# edison_gpio.net
KiCad netlist of a schematic drawn in Altium Designer
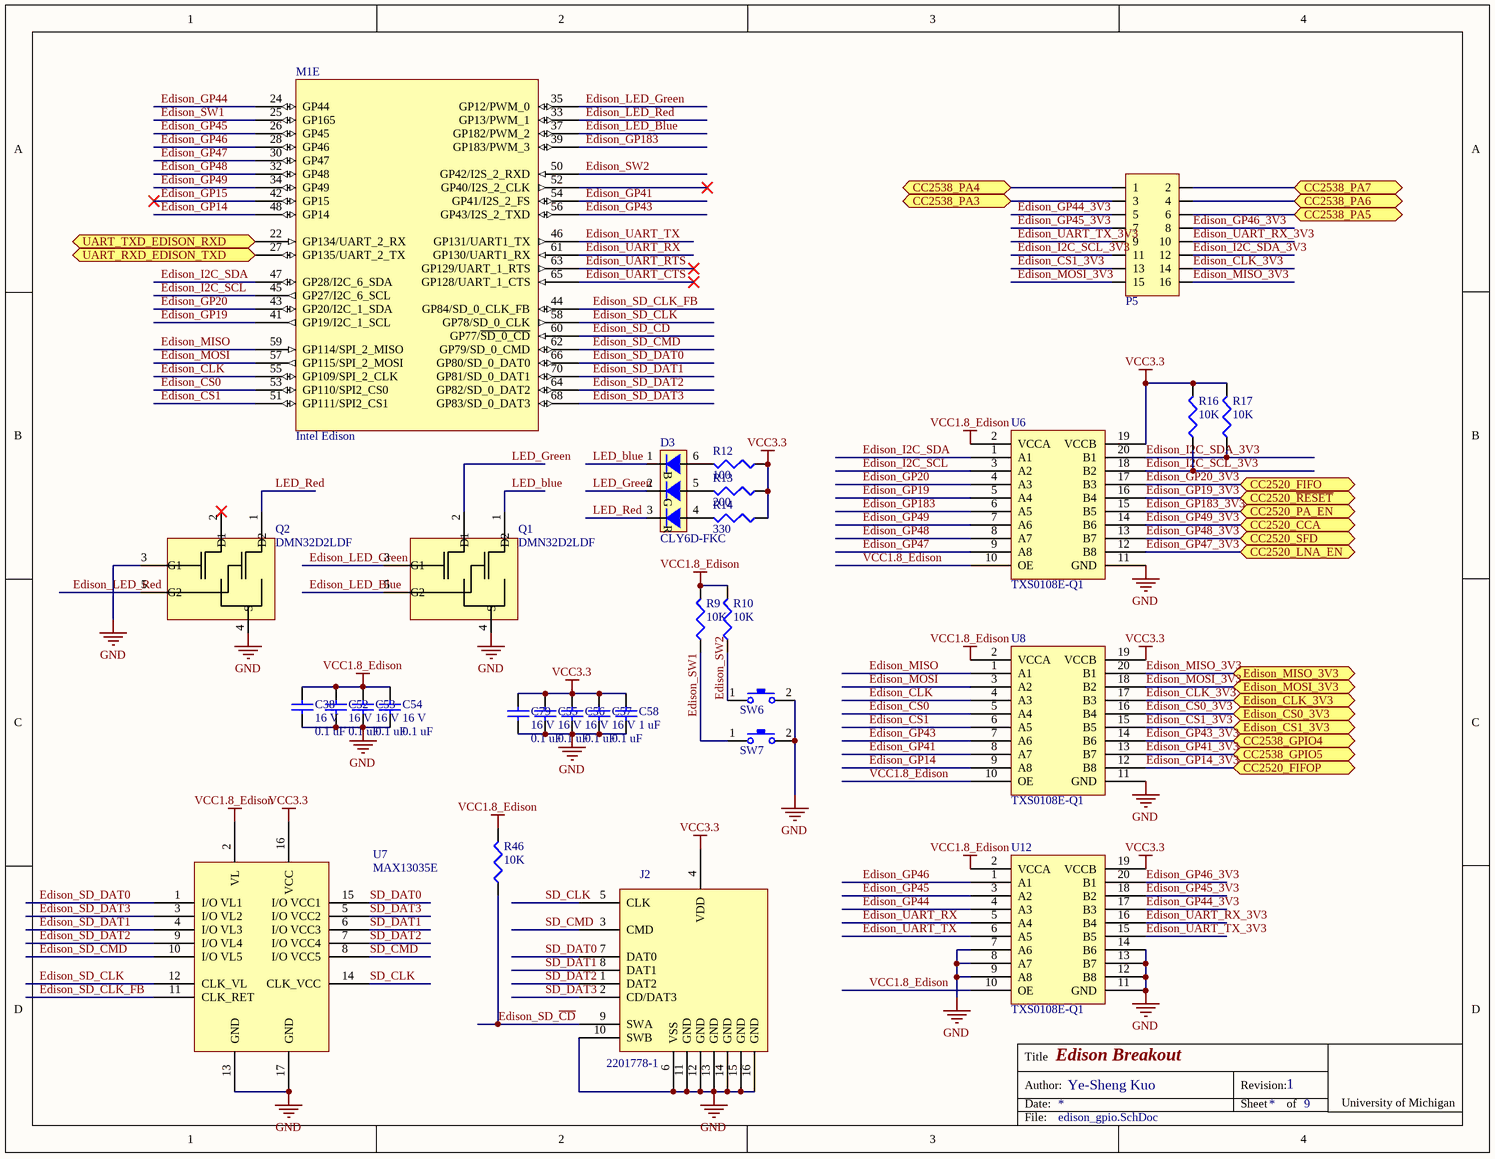
[diagram p0: edison_gpio.SchDoc]

(export (version "E")
  (design (tool "Eeschema 10.0.6"))
  (components
    (comp (ref "C38")
      (value "0.1 uF")
      (footprint "0402")
      (description "Ceramic capacitor, 0.1u, 16 V, 0402 package")
      (fields
        (field (name "VOLTAGE RATED") "16 V")
        (field (name "TOLERANCE") "10%")
        (field (name "Comment") "Ceramic capacitor")
      )
      (libsource (lib "rlc") (part "C_0.1u_16V_0402_ceramic"))
    )
    (comp (ref "C52")
      (value "0.1 uF")
      (footprint "0402")
      (description "Ceramic capacitor, 0.1u, 16 V, 0402 package")
      (fields
        (field (name "VOLTAGE RATED") "16 V")
        (field (name "TOLERANCE") "10%")
        (field (name "Comment") "Ceramic capacitor")
      )
      (libsource (lib "rlc") (part "C_0.1u_16V_0402_ceramic"))
    )
    (comp (ref "C53")
      (value "0.1 uF")
      (footprint "0402")
      (description "Ceramic capacitor, 0.1u, 16 V, 0402 package")
      (fields
        (field (name "VOLTAGE RATED") "16 V")
        (field (name "TOLERANCE") "10%")
        (field (name "Comment") "Ceramic capacitor")
      )
      (libsource (lib "rlc") (part "C_0.1u_16V_0402_ceramic"))
    )
    (comp (ref "C54")
      (value "0.1 uF")
      (footprint "0402")
      (description "Ceramic capacitor, 0.1u, 16 V, 0402 package")
      (fields
        (field (name "VOLTAGE RATED") "16 V")
        (field (name "TOLERANCE") "10%")
        (field (name "Comment") "Ceramic capacitor")
      )
      (libsource (lib "rlc") (part "C_0.1u_16V_0402_ceramic"))
    )
    (comp (ref "C55")
      (value "0.1 uF")
      (footprint "0402")
      (description "Ceramic capacitor, 0.1u, 16 V, 0402 package")
      (fields
        (field (name "VOLTAGE RATED") "16 V")
        (field (name "TOLERANCE") "10%")
        (field (name "Comment") "Ceramic capacitor")
      )
      (libsource (lib "rlc") (part "C_0.1u_16V_0402_ceramic"))
    )
    (comp (ref "C56")
      (value "0.1 uF")
      (footprint "0402")
      (description "Ceramic capacitor, 0.1u, 16 V, 0402 package")
      (fields
        (field (name "VOLTAGE RATED") "16 V")
        (field (name "TOLERANCE") "10%")
        (field (name "Comment") "Ceramic capacitor")
      )
      (libsource (lib "rlc") (part "C_0.1u_16V_0402_ceramic"))
    )
    (comp (ref "C57")
      (value "0.1 uF")
      (footprint "0402")
      (description "Ceramic capacitor, 0.1u, 16 V, 0402 package")
      (fields
        (field (name "VOLTAGE RATED") "16 V")
        (field (name "TOLERANCE") "10%")
        (field (name "Comment") "Ceramic capacitor")
      )
      (libsource (lib "rlc") (part "C_0.1u_16V_0402_ceramic"))
    )
    (comp (ref "C58")
      (value "1 uF")
      (footprint "0402")
      (description "Ceramic capacitor, 1 uF, 16V, 0402 package")
      (fields (field (name "TOLERANCE") "10%") (field (name "Comment") "Ceramic capacitor"))
      (libsource (lib "rlc") (part "C_1u_16V_0402_ceramic"))
    )
    (comp (ref "C79")
      (value "0.1 uF")
      (footprint "0402")
      (description "Ceramic capacitor, 0.1u, 16 V, 0402 package")
      (fields
        (field (name "VOLTAGE RATED") "16 V")
        (field (name "TOLERANCE") "10%")
        (field (name "Comment") "Ceramic capacitor")
      )
      (libsource (lib "rlc") (part "C_0.1u_16V_0402_ceramic"))
    )
    (comp (ref "D3")
      (value "CLY6D-FKC")
      (footprint "PLCC6")
      (description "CREE PLCC6 3 in 1 SMD LED")
      (libsource (lib "rlc") (part "D_CLY6D-FKC"))
    )
    (comp (ref "J2")
      (value "2201778-1")
      (footprint "2201778-1")
      (description "Micro SD Slot")
      (libsource (lib "connectors") (part "2201778-1"))
    )
    (comp (ref "M1")
      (value "Intel Edison")
      (footprint "Intel Edison mating")
      (libsource (lib "edison") (part "Intel Edison"))
    )
    (comp (ref "P5")
      (value "2 x 8 header")
      (footprint "2x8 header")
      (description "100 mils standard header")
      (libsource (lib "connectors") (part "2 x 8 header"))
    )
    (comp (ref "Q1")
      (value "DMN32D2LDF")
      (footprint "SOT-353-5")
      (description "Common Source Dual N-Channel MOSFET")
      (libsource (lib "transistors") (part "DMN32D2LDF"))
    )
    (comp (ref "Q2")
      (value "DMN32D2LDF")
      (footprint "SOT-353-5")
      (description "Common Source Dual N-Channel MOSFET")
      (libsource (lib "transistors") (part "DMN32D2LDF"))
    )
    (comp (ref "R9")
      (value "10K")
      (footprint "0402")
      (description "Chip resistor, 10K, 0402 package")
      (fields (field (name "TOLERANCE") "1%") (field (name "POWER") "1/16 W"))
      (libsource (lib "rlc") (part "R_10K_0402"))
    )
    (comp (ref "R10")
      (value "10K")
      (footprint "0402")
      (description "Chip resistor, 10K, 0402 package")
      (fields (field (name "TOLERANCE") "1%") (field (name "POWER") "1/16 W"))
      (libsource (lib "rlc") (part "R_10K_0402"))
    )
    (comp (ref "R12")
      (value "100")
      (footprint "0402")
      (description "Chip resistor, 100, 0402 package")
      (fields (field (name "TOLERANCE") "1%") (field (name "POWER") "1/16 W"))
      (libsource (lib "rlc") (part "R_100_0402"))
    )
    (comp (ref "R13")
      (value "200")
      (footprint "0402")
      (description "Chip resistor, 200, 0402 package")
      (fields (field (name "TOLERANCE") "1%") (field (name "POWER") "1/16 W"))
      (libsource (lib "rlc") (part "R_200_0402"))
    )
    (comp (ref "R14")
      (value "330")
      (footprint "0402")
      (description "Chip resistor, 330, 0402 package")
      (fields (field (name "TOLERANCE") "1%") (field (name "POWER") "1/16 W"))
      (libsource (lib "rlc") (part "R_330_0402"))
    )
    (comp (ref "R16")
      (value "10K")
      (footprint "0402")
      (description "Chip resistor, 10K, 0402 package")
      (fields (field (name "TOLERANCE") "1%") (field (name "POWER") "1/16 W"))
      (libsource (lib "rlc") (part "R_10K_0402"))
    )
    (comp (ref "R17")
      (value "10K")
      (footprint "0402")
      (description "Chip resistor, 10K, 0402 package")
      (fields (field (name "TOLERANCE") "1%") (field (name "POWER") "1/16 W"))
      (libsource (lib "rlc") (part "R_10K_0402"))
    )
    (comp (ref "R46")
      (value "10K")
      (footprint "0402")
      (description "Chip resistor, 10K, 0402 package")
      (fields (field (name "TOLERANCE") "1%") (field (name "POWER") "1/16 W"))
      (libsource (lib "rlc") (part "R_10K_0402"))
    )
    (comp (ref "SW6")
      (value "1825027-8")
      (footprint "1825027-8")
      (description "SWITCH TACTILE SPST-NO 0.05A 24V")
      (libsource (lib "switches") (part "1825027-8"))
    )
    (comp (ref "SW7")
      (value "1825027-8")
      (footprint "1825027-8")
      (description "SWITCH TACTILE SPST-NO 0.05A 24V")
      (libsource (lib "switches") (part "1825027-8"))
    )
    (comp (ref "U6")
      (value "TXS0108E-Q1")
      (footprint "TSSOP-20")
      (libsource (lib "level_shifter") (part "TXS0108E-Q1"))
    )
    (comp (ref "U7")
      (value "MAX13035E")
      (footprint "TQFN-16")
      (description "6-Channel High-Speed Logic-Level Translators")
      (libsource (lib "level_shifter") (part "MAX13035E"))
    )
    (comp (ref "U8")
      (value "TXS0108E-Q1")
      (footprint "TSSOP-20")
      (libsource (lib "level_shifter") (part "TXS0108E-Q1"))
    )
    (comp (ref "U12")
      (value "TXS0108E-Q1")
      (footprint "TSSOP-20")
      (libsource (lib "level_shifter") (part "TXS0108E-Q1"))
    )
  )
  (nets
    (net (code "1") (name "/CC2538_PA3") (class "Default")
      (node (ref "P5") (pin "3") (pinfunction "3_3") (pintype "passive"))
    )
    (net (code "2") (name "/CC2538_PA4") (class "Default")
      (node (ref "P5") (pin "1") (pinfunction "1_1") (pintype "passive"))
    )
    (net (code "3") (name "/CC2538_PA5") (class "Default")
      (node (ref "P5") (pin "6") (pinfunction "6_6") (pintype "passive"))
    )
    (net (code "4") (name "/CC2538_PA6") (class "Default")
      (node (ref "P5") (pin "4") (pinfunction "4_4") (pintype "passive"))
    )
    (net (code "5") (name "/CC2538_PA7") (class "Default")
      (node (ref "P5") (pin "2") (pinfunction "2_2") (pintype "passive"))
    )
    (net (code "6") (name "/Edison_CLK") (class "Default")
      (node (ref "M1") (pin "55") (pinfunction "GP109/SPI_2_CLK_55") (pintype "bidirectional"))
      (node (ref "U8") (pin "4") (pinfunction "A3_4") (pintype "passive"))
    )
    (net (code "7") (name "/Edison_CLK_3V3") (class "Default")
      (node (ref "P5") (pin "14") (pinfunction "14_14") (pintype "passive"))
      (node (ref "U8") (pin "17") (pinfunction "B3_17") (pintype "passive"))
    )
    (net (code "8") (name "/Edison_CS0") (class "Default")
      (node (ref "M1") (pin "53") (pinfunction "GP110/SPI2_CS0_53") (pintype "bidirectional"))
      (node (ref "U8") (pin "5") (pinfunction "A4_5") (pintype "passive"))
    )
    (net (code "9") (name "/Edison_CS0_3V3") (class "Default")
      (node (ref "U8") (pin "16") (pinfunction "B4_16") (pintype "passive"))
    )
    (net (code "10") (name "/Edison_CS1") (class "Default")
      (node (ref "M1") (pin "51") (pinfunction "GP111/SPI2_CS1_51") (pintype "bidirectional"))
      (node (ref "U8") (pin "6") (pinfunction "A5_6") (pintype "passive"))
    )
    (net (code "11") (name "/Edison_CS1_3V3") (class "Default")
      (node (ref "P5") (pin "13") (pinfunction "13_13") (pintype "passive"))
      (node (ref "U8") (pin "15") (pinfunction "B5_15") (pintype "passive"))
    )
    (net (code "12") (name "/Edison_GP14") (class "Default")
      (node (ref "M1") (pin "48") (pinfunction "GP14_48") (pintype "bidirectional"))
      (node (ref "U8") (pin "9") (pinfunction "A8_9") (pintype "passive"))
    )
    (net (code "13") (name "/Edison_GP14_3V3") (class "Default")
      (node (ref "U8") (pin "12") (pinfunction "B8_12") (pintype "passive"))
    )
    (net (code "14") (name "/Edison_GP15") (class "Default")
      (node (ref "M1") (pin "42") (pinfunction "GP15_42") (pintype "bidirectional+no_connect"))
    )
    (net (code "15") (name "/Edison_GP19") (class "Default")
      (node (ref "M1") (pin "41") (pinfunction "GP19/I2C_1_SCL_41") (pintype "output"))
      (node (ref "U6") (pin "5") (pinfunction "A4_5") (pintype "passive"))
    )
    (net (code "16") (name "/Edison_GP19_3V3") (class "Default")
      (node (ref "U6") (pin "16") (pinfunction "B4_16") (pintype "passive"))
    )
    (net (code "17") (name "/Edison_GP20") (class "Default")
      (node (ref "M1") (pin "43") (pinfunction "GP20/I2C_1_SDA_43") (pintype "bidirectional"))
      (node (ref "U6") (pin "4") (pinfunction "A3_4") (pintype "passive"))
    )
    (net (code "18") (name "/Edison_GP20_3V3") (class "Default")
      (node (ref "U6") (pin "17") (pinfunction "B3_17") (pintype "passive"))
    )
    (net (code "19") (name "/Edison_GP41") (class "Default")
      (node (ref "M1") (pin "54") (pinfunction "GP41/I2S_2_FS_54") (pintype "bidirectional"))
      (node (ref "U8") (pin "8") (pinfunction "A7_8") (pintype "passive"))
    )
    (net (code "20") (name "/Edison_GP41_3V3") (class "Default")
      (node (ref "U8") (pin "13") (pinfunction "B7_13") (pintype "passive"))
    )
    (net (code "21") (name "/Edison_GP43") (class "Default")
      (node (ref "M1") (pin "56") (pinfunction "GP43/I2S_2_TXD_56") (pintype "bidirectional"))
      (node (ref "U8") (pin "7") (pinfunction "A6_7") (pintype "passive"))
    )
    (net (code "22") (name "/Edison_GP43_3V3") (class "Default")
      (node (ref "U8") (pin "14") (pinfunction "B6_14") (pintype "passive"))
    )
    (net (code "23") (name "/Edison_GP44") (class "Default")
      (node (ref "M1") (pin "24") (pinfunction "GP44_24") (pintype "bidirectional"))
      (node (ref "U12") (pin "4") (pinfunction "A3_4") (pintype "passive"))
    )
    (net (code "24") (name "/Edison_GP44_3V3") (class "Default")
      (node (ref "P5") (pin "5") (pinfunction "5_5") (pintype "passive"))
      (node (ref "U12") (pin "17") (pinfunction "B3_17") (pintype "passive"))
    )
    (net (code "25") (name "/Edison_GP45") (class "Default")
      (node (ref "M1") (pin "26") (pinfunction "GP45_26") (pintype "bidirectional"))
      (node (ref "U12") (pin "3") (pinfunction "A2_3") (pintype "passive"))
    )
    (net (code "26") (name "/Edison_GP45_3V3") (class "Default")
      (node (ref "P5") (pin "7") (pinfunction "7_7") (pintype "passive"))
      (node (ref "U12") (pin "18") (pinfunction "B2_18") (pintype "passive"))
    )
    (net (code "27") (name "/Edison_GP46") (class "Default")
      (node (ref "M1") (pin "28") (pinfunction "GP46_28") (pintype "bidirectional"))
      (node (ref "U12") (pin "1") (pinfunction "A1_1") (pintype "passive"))
    )
    (net (code "28") (name "/Edison_GP46_3V3") (class "Default")
      (node (ref "P5") (pin "8") (pinfunction "8_8") (pintype "passive"))
      (node (ref "U12") (pin "20") (pinfunction "B1_20") (pintype "passive"))
    )
    (net (code "29") (name "/Edison_GP47") (class "Default")
      (node (ref "M1") (pin "30") (pinfunction "GP47_30") (pintype "bidirectional"))
      (node (ref "U6") (pin "9") (pinfunction "A8_9") (pintype "passive"))
    )
    (net (code "30") (name "/Edison_GP47_3V3") (class "Default")
      (node (ref "U6") (pin "12") (pinfunction "B8_12") (pintype "passive"))
    )
    (net (code "31") (name "/Edison_GP48") (class "Default")
      (node (ref "M1") (pin "32") (pinfunction "GP48_32") (pintype "bidirectional"))
      (node (ref "U6") (pin "8") (pinfunction "A7_8") (pintype "passive"))
    )
    (net (code "32") (name "/Edison_GP48_3V3") (class "Default")
      (node (ref "U6") (pin "13") (pinfunction "B7_13") (pintype "passive"))
    )
    (net (code "33") (name "/Edison_GP49") (class "Default")
      (node (ref "M1") (pin "34") (pinfunction "GP49_34") (pintype "bidirectional"))
      (node (ref "U6") (pin "7") (pinfunction "A6_7") (pintype "passive"))
    )
    (net (code "34") (name "/Edison_GP49_3V3") (class "Default")
      (node (ref "U6") (pin "14") (pinfunction "B6_14") (pintype "passive"))
    )
    (net (code "35") (name "/Edison_GP183") (class "Default")
      (node (ref "M1") (pin "39") (pinfunction "GP183/PWM_3_39") (pintype "bidirectional"))
      (node (ref "U6") (pin "6") (pinfunction "A5_6") (pintype "passive"))
    )
    (net (code "36") (name "/Edison_GP183_3V3") (class "Default")
      (node (ref "U6") (pin "15") (pinfunction "B5_15") (pintype "passive"))
    )
    (net (code "37") (name "/Edison_I2C_SCL") (class "Default")
      (node (ref "M1") (pin "45") (pinfunction "GP27/I2C_6_SCL_45") (pintype "output"))
      (node (ref "U6") (pin "3") (pinfunction "A2_3") (pintype "passive"))
    )
    (net (code "38") (name "/Edison_I2C_SCL_3V3") (class "Default")
      (node (ref "P5") (pin "11") (pinfunction "11_11") (pintype "passive"))
      (node (ref "R16") (pin "2") (pintype "passive"))
      (node (ref "U6") (pin "18") (pinfunction "B2_18") (pintype "passive"))
    )
    (net (code "39") (name "/Edison_I2C_SDA") (class "Default")
      (node (ref "M1") (pin "47") (pinfunction "GP28/I2C_6_SDA_47") (pintype "bidirectional"))
      (node (ref "U6") (pin "1") (pinfunction "A1_1") (pintype "passive"))
    )
    (net (code "40") (name "/Edison_I2C_SDA_3V3") (class "Default")
      (node (ref "P5") (pin "12") (pinfunction "12_12") (pintype "passive"))
      (node (ref "R17") (pin "2") (pintype "passive"))
      (node (ref "U6") (pin "20") (pinfunction "B1_20") (pintype "passive"))
    )
    (net (code "41") (name "/Edison_LED_Blue") (class "Default")
      (node (ref "M1") (pin "37") (pinfunction "GP182/PWM_2_37") (pintype "bidirectional"))
      (node (ref "Q1") (pin "5") (pinfunction "G2_5") (pintype "passive"))
    )
    (net (code "42") (name "/Edison_LED_Green") (class "Default")
      (node (ref "M1") (pin "35") (pinfunction "GP12/PWM_0_35") (pintype "bidirectional"))
      (node (ref "Q1") (pin "3") (pinfunction "G1_3") (pintype "passive"))
    )
    (net (code "43") (name "/Edison_LED_Red") (class "Default")
      (node (ref "M1") (pin "33") (pinfunction "GP13/PWM_1_33") (pintype "bidirectional"))
      (node (ref "Q2") (pin "5") (pinfunction "G2_5") (pintype "passive"))
    )
    (net (code "44") (name "/Edison_MISO") (class "Default")
      (node (ref "M1") (pin "59") (pinfunction "GP114/SPI_2_MISO_59") (pintype "input"))
      (node (ref "U8") (pin "1") (pinfunction "A1_1") (pintype "passive"))
    )
    (net (code "45") (name "/Edison_MISO_3V3") (class "Default")
      (node (ref "P5") (pin "16") (pinfunction "16_16") (pintype "passive"))
      (node (ref "U8") (pin "20") (pinfunction "B1_20") (pintype "passive"))
    )
    (net (code "46") (name "/Edison_MOSI") (class "Default")
      (node (ref "M1") (pin "57") (pinfunction "GP115/SPI_2_MOSI_57") (pintype "output"))
      (node (ref "U8") (pin "3") (pinfunction "A2_3") (pintype "passive"))
    )
    (net (code "47") (name "/Edison_MOSI_3V3") (class "Default")
      (node (ref "P5") (pin "15") (pinfunction "15_15") (pintype "passive"))
      (node (ref "U8") (pin "18") (pinfunction "B2_18") (pintype "passive"))
    )
    (net (code "48") (name "/Edison_SD_CLK") (class "Default")
      (node (ref "M1") (pin "58") (pinfunction "GP78/SD_0_CLK_58") (pintype "output"))
      (node (ref "U7") (pin "12") (pinfunction "CLK_VL_12") (pintype "passive"))
    )
    (net (code "49") (name "/Edison_SD_CLK_FB") (class "Default")
      (node (ref "M1") (pin "44") (pinfunction "GP84/SD_0_CLK_FB_44") (pintype "bidirectional"))
      (node (ref "U7") (pin "11") (pinfunction "CLK_RET_11") (pintype "passive"))
    )
    (net (code "50") (name "/Edison_SD_CMD") (class "Default")
      (node (ref "M1") (pin "62") (pinfunction "GP79/SD_0_CMD_62") (pintype "bidirectional"))
      (node (ref "U7") (pin "10") (pinfunction "I/O_VL5_10") (pintype "passive"))
    )
    (net (code "51") (name "/Edison_SD_DAT0") (class "Default")
      (node (ref "M1") (pin "66") (pinfunction "GP80/SD_0_DAT0_66") (pintype "bidirectional"))
      (node (ref "U7") (pin "1") (pinfunction "I/O_VL1_1") (pintype "passive"))
    )
    (net (code "52") (name "/Edison_SD_DAT1") (class "Default")
      (node (ref "M1") (pin "70") (pinfunction "GP81/SD_0_DAT1_70") (pintype "bidirectional"))
      (node (ref "U7") (pin "4") (pinfunction "I/O_VL3_4") (pintype "passive"))
    )
    (net (code "53") (name "/Edison_SD_DAT2") (class "Default")
      (node (ref "M1") (pin "64") (pinfunction "GP82/SD_0_DAT2_64") (pintype "bidirectional"))
      (node (ref "U7") (pin "9") (pinfunction "I/O_VL4_9") (pintype "passive"))
    )
    (net (code "54") (name "/Edison_SD_DAT3") (class "Default")
      (node (ref "M1") (pin "68") (pinfunction "GP83/SD_0_DAT3_68") (pintype "bidirectional"))
      (node (ref "U7") (pin "3") (pinfunction "I/O_VL2_3") (pintype "passive"))
    )
    (net (code "55") (name "/Edison_SD_~{CD}") (class "Default")
      (node (ref "J2") (pin "9") (pinfunction "SWA_9") (pintype "passive"))
      (node (ref "M1") (pin "60") (pinfunction "GP77/~{SD_0_CD}_60") (pintype "input"))
      (node (ref "R46") (pin "2") (pintype "passive"))
    )
    (net (code "56") (name "/Edison_SW1") (class "Default")
      (node (ref "M1") (pin "25") (pinfunction "GP165_25") (pintype "bidirectional"))
      (node (ref "R9") (pin "2") (pintype "passive"))
      (node (ref "SW7") (pin "1") (pinfunction "1_1") (pintype "passive"))
    )
    (net (code "57") (name "/Edison_SW2") (class "Default")
      (node (ref "M1") (pin "50") (pinfunction "GP42/I2S_2_RXD_50") (pintype "input"))
      (node (ref "R10") (pin "2") (pintype "passive"))
      (node (ref "SW6") (pin "1") (pinfunction "1_1") (pintype "passive"))
    )
    (net (code "58") (name "/Edison_UART_CTS") (class "Default")
      (node (ref "M1") (pin "65") (pinfunction "GP128/UART_1_CTS_65") (pintype "input+no_connect"))
    )
    (net (code "59") (name "/Edison_UART_RTS") (class "Default")
      (node (ref "M1") (pin "63") (pinfunction "GP129/UART_1_RTS_63") (pintype "output+no_connect"))
    )
    (net (code "60") (name "/Edison_UART_RX") (class "Default")
      (node (ref "M1") (pin "61") (pinfunction "GP130/UART1_RX_61") (pintype "input"))
      (node (ref "U12") (pin "5") (pinfunction "A4_5") (pintype "passive"))
    )
    (net (code "61") (name "/Edison_UART_RX_3V3") (class "Default")
      (node (ref "P5") (pin "10") (pinfunction "10_10") (pintype "passive"))
      (node (ref "U12") (pin "16") (pinfunction "B4_16") (pintype "passive"))
    )
    (net (code "62") (name "/Edison_UART_TX") (class "Default")
      (node (ref "M1") (pin "46") (pinfunction "GP131/UART1_TX_46") (pintype "output"))
      (node (ref "U12") (pin "6") (pinfunction "A5_6") (pintype "passive"))
    )
    (net (code "63") (name "/Edison_UART_TX_3V3") (class "Default")
      (node (ref "P5") (pin "9") (pinfunction "9_9") (pintype "passive"))
      (node (ref "U12") (pin "15") (pinfunction "B5_15") (pintype "passive"))
    )
    (net (code "64") (name "/LED_Green") (class "Default")
      (node (ref "D3") (pin "2") (pintype "passive"))
      (node (ref "Q1") (pin "2") (pinfunction "D1_2") (pintype "passive"))
    )
    (net (code "65") (name "/LED_Red") (class "Default")
      (node (ref "D3") (pin "3") (pinfunction "3_3") (pintype "passive"))
      (node (ref "Q2") (pin "1") (pinfunction "D2_1") (pintype "passive"))
    )
    (net (code "66") (name "/LED_blue") (class "Default")
      (node (ref "D3") (pin "1") (pintype "passive"))
      (node (ref "Q1") (pin "1") (pinfunction "D2_1") (pintype "passive"))
    )
    (net (code "67") (name "/SD_CLK") (class "Default")
      (node (ref "J2") (pin "5") (pinfunction "CLK_5") (pintype "passive"))
      (node (ref "U7") (pin "14") (pinfunction "CLK_VCC_14") (pintype "passive"))
    )
    (net (code "68") (name "/SD_CMD") (class "Default")
      (node (ref "J2") (pin "3") (pinfunction "CMD_3") (pintype "passive"))
      (node (ref "U7") (pin "8") (pinfunction "I/O_VCC5_8") (pintype "passive"))
    )
    (net (code "69") (name "/SD_DAT0") (class "Default")
      (node (ref "J2") (pin "7") (pinfunction "DAT0_7") (pintype "passive"))
      (node (ref "U7") (pin "15") (pinfunction "I/O_VCC1_15") (pintype "passive"))
    )
    (net (code "70") (name "/SD_DAT1") (class "Default")
      (node (ref "J2") (pin "8") (pinfunction "DAT1_8") (pintype "passive"))
      (node (ref "U7") (pin "6") (pinfunction "I/O_VCC3_6") (pintype "passive"))
    )
    (net (code "71") (name "/SD_DAT2") (class "Default")
      (node (ref "J2") (pin "1") (pinfunction "DAT2_1") (pintype "passive"))
      (node (ref "U7") (pin "7") (pinfunction "I/O_VCC4_7") (pintype "passive"))
    )
    (net (code "72") (name "/SD_DAT3") (class "Default")
      (node (ref "J2") (pin "2") (pinfunction "CD/DAT3_2") (pintype "passive"))
      (node (ref "U7") (pin "5") (pinfunction "I/O_VCC2_5") (pintype "passive"))
    )
    (net (code "73") (name "/UART_RXD_EDISON_TXD") (class "Default")
      (node (ref "M1") (pin "27") (pinfunction "GP135/UART_2_TX_27") (pintype "bidirectional"))
    )
    (net (code "74") (name "/UART_TXD_EDISON_RXD") (class "Default")
      (node (ref "M1") (pin "22") (pinfunction "GP134/UART_2_RX_22") (pintype "input"))
    )
    (net (code "75") (name "GND") (class "Default")
      (node (ref "C38") (pin "2") (pintype "passive"))
      (node (ref "C52") (pin "2") (pintype "passive"))
      (node (ref "C53") (pin "2") (pintype "passive"))
      (node (ref "C54") (pin "2") (pintype "passive"))
      (node (ref "C55") (pin "2") (pintype "passive"))
      (node (ref "C56") (pin "2") (pintype "passive"))
      (node (ref "C57") (pin "2") (pintype "passive"))
      (node (ref "C58") (pin "2") (pintype "passive"))
      (node (ref "C79") (pin "2") (pintype "passive"))
      (node (ref "J2") (pin "10") (pinfunction "SWB_10") (pintype "passive"))
      (node (ref "J2") (pin "11") (pinfunction "GND_11") (pintype "passive"))
      (node (ref "J2") (pin "12") (pinfunction "GND_12") (pintype "passive"))
      (node (ref "J2") (pin "13") (pinfunction "GND_13") (pintype "passive"))
      (node (ref "J2") (pin "14") (pinfunction "GND_14") (pintype "passive"))
      (node (ref "J2") (pin "15") (pinfunction "GND_15") (pintype "passive"))
      (node (ref "J2") (pin "16") (pinfunction "GND_16") (pintype "passive"))
      (node (ref "J2") (pin "6") (pinfunction "VSS_6") (pintype "passive"))
      (node (ref "Q1") (pin "4") (pinfunction "S_4") (pintype "passive"))
      (node (ref "Q2") (pin "3") (pinfunction "G1_3") (pintype "passive"))
      (node (ref "Q2") (pin "4") (pinfunction "S_4") (pintype "passive"))
      (node (ref "SW6") (pin "2") (pinfunction "2_2") (pintype "passive"))
      (node (ref "SW7") (pin "2") (pinfunction "2_2") (pintype "passive"))
      (node (ref "U12") (pin "11") (pinfunction "GND_11") (pintype "passive"))
      (node (ref "U12") (pin "12") (pinfunction "B8_12") (pintype "passive"))
      (node (ref "U12") (pin "13") (pinfunction "B7_13") (pintype "passive"))
      (node (ref "U12") (pin "14") (pinfunction "B6_14") (pintype "passive"))
      (node (ref "U12") (pin "7") (pinfunction "A6_7") (pintype "passive"))
      (node (ref "U12") (pin "8") (pinfunction "A7_8") (pintype "passive"))
      (node (ref "U12") (pin "9") (pinfunction "A8_9") (pintype "passive"))
      (node (ref "U6") (pin "11") (pinfunction "GND_11") (pintype "passive"))
      (node (ref "U7") (pin "13") (pinfunction "GND_13") (pintype "passive"))
      (node (ref "U7") (pin "17") (pinfunction "GND_17") (pintype "passive"))
      (node (ref "U8") (pin "11") (pinfunction "GND_11") (pintype "passive"))
    )
    (net (code "76") (name "Net-(D3-Pad4)") (class "Default")
      (node (ref "D3") (pin "4") (pinfunction "4_4") (pintype "passive"))
      (node (ref "R14") (pin "1") (pintype "passive"))
    )
    (net (code "77") (name "Net-(D3-Pad5)") (class "Default")
      (node (ref "D3") (pin "5") (pinfunction "5_5") (pintype "passive"))
      (node (ref "R13") (pin "1") (pintype "passive"))
    )
    (net (code "78") (name "Net-(D3-Pad6)") (class "Default")
      (node (ref "D3") (pin "6") (pinfunction "6_6") (pintype "passive"))
      (node (ref "R12") (pin "1") (pintype "passive"))
    )
    (net (code "79") (name "VCC1.8_Edison") (class "Default")
      (node (ref "C38") (pin "1") (pintype "passive"))
      (node (ref "C52") (pin "1") (pintype "passive"))
      (node (ref "C53") (pin "1") (pintype "passive"))
      (node (ref "C54") (pin "1") (pintype "passive"))
      (node (ref "R10") (pin "1") (pintype "passive"))
      (node (ref "R46") (pin "1") (pintype "passive"))
      (node (ref "R9") (pin "1") (pintype "passive"))
      (node (ref "U12") (pin "10") (pinfunction "OE_10") (pintype "passive"))
      (node (ref "U12") (pin "2") (pinfunction "VCCA_2") (pintype "passive"))
      (node (ref "U6") (pin "10") (pinfunction "OE_10") (pintype "passive"))
      (node (ref "U6") (pin "2") (pinfunction "VCCA_2") (pintype "passive"))
      (node (ref "U7") (pin "2") (pinfunction "VL_2") (pintype "passive"))
      (node (ref "U8") (pin "10") (pinfunction "OE_10") (pintype "passive"))
      (node (ref "U8") (pin "2") (pinfunction "VCCA_2") (pintype "passive"))
    )
    (net (code "80") (name "VCC3.3") (class "Default")
      (node (ref "C55") (pin "1") (pintype "passive"))
      (node (ref "C56") (pin "1") (pintype "passive"))
      (node (ref "C57") (pin "1") (pintype "passive"))
      (node (ref "C58") (pin "1") (pintype "passive"))
      (node (ref "C79") (pin "1") (pintype "passive"))
      (node (ref "J2") (pin "4") (pinfunction "VDD_4") (pintype "passive"))
      (node (ref "R12") (pin "2") (pintype "passive"))
      (node (ref "R13") (pin "2") (pintype "passive"))
      (node (ref "R14") (pin "2") (pintype "passive"))
      (node (ref "R16") (pin "1") (pintype "passive"))
      (node (ref "R17") (pin "1") (pintype "passive"))
      (node (ref "U12") (pin "19") (pinfunction "VCCB_19") (pintype "passive"))
      (node (ref "U6") (pin "19") (pinfunction "VCCB_19") (pintype "passive"))
      (node (ref "U7") (pin "16") (pinfunction "VCC_16") (pintype "passive"))
      (node (ref "U8") (pin "19") (pinfunction "VCCB_19") (pintype "passive"))
    )
    (net (code "81") (name "unconnected-(M1E-GP40{slash}I2S_2_CLK-Pad52)") (class "Default")
      (node (ref "M1") (pin "52") (pinfunction "GP40/I2S_2_CLK_52") (pintype "output+no_connect"))
    )
    (net (code "82") (name "unconnected-(Q2-D1-Pad2)") (class "Default")
      (node (ref "Q2") (pin "2") (pinfunction "D1_2") (pintype "passive+no_connect"))
    )
  )
)
